# MicroController.net
KiCad netlist of a schematic drawn in Altium Designer
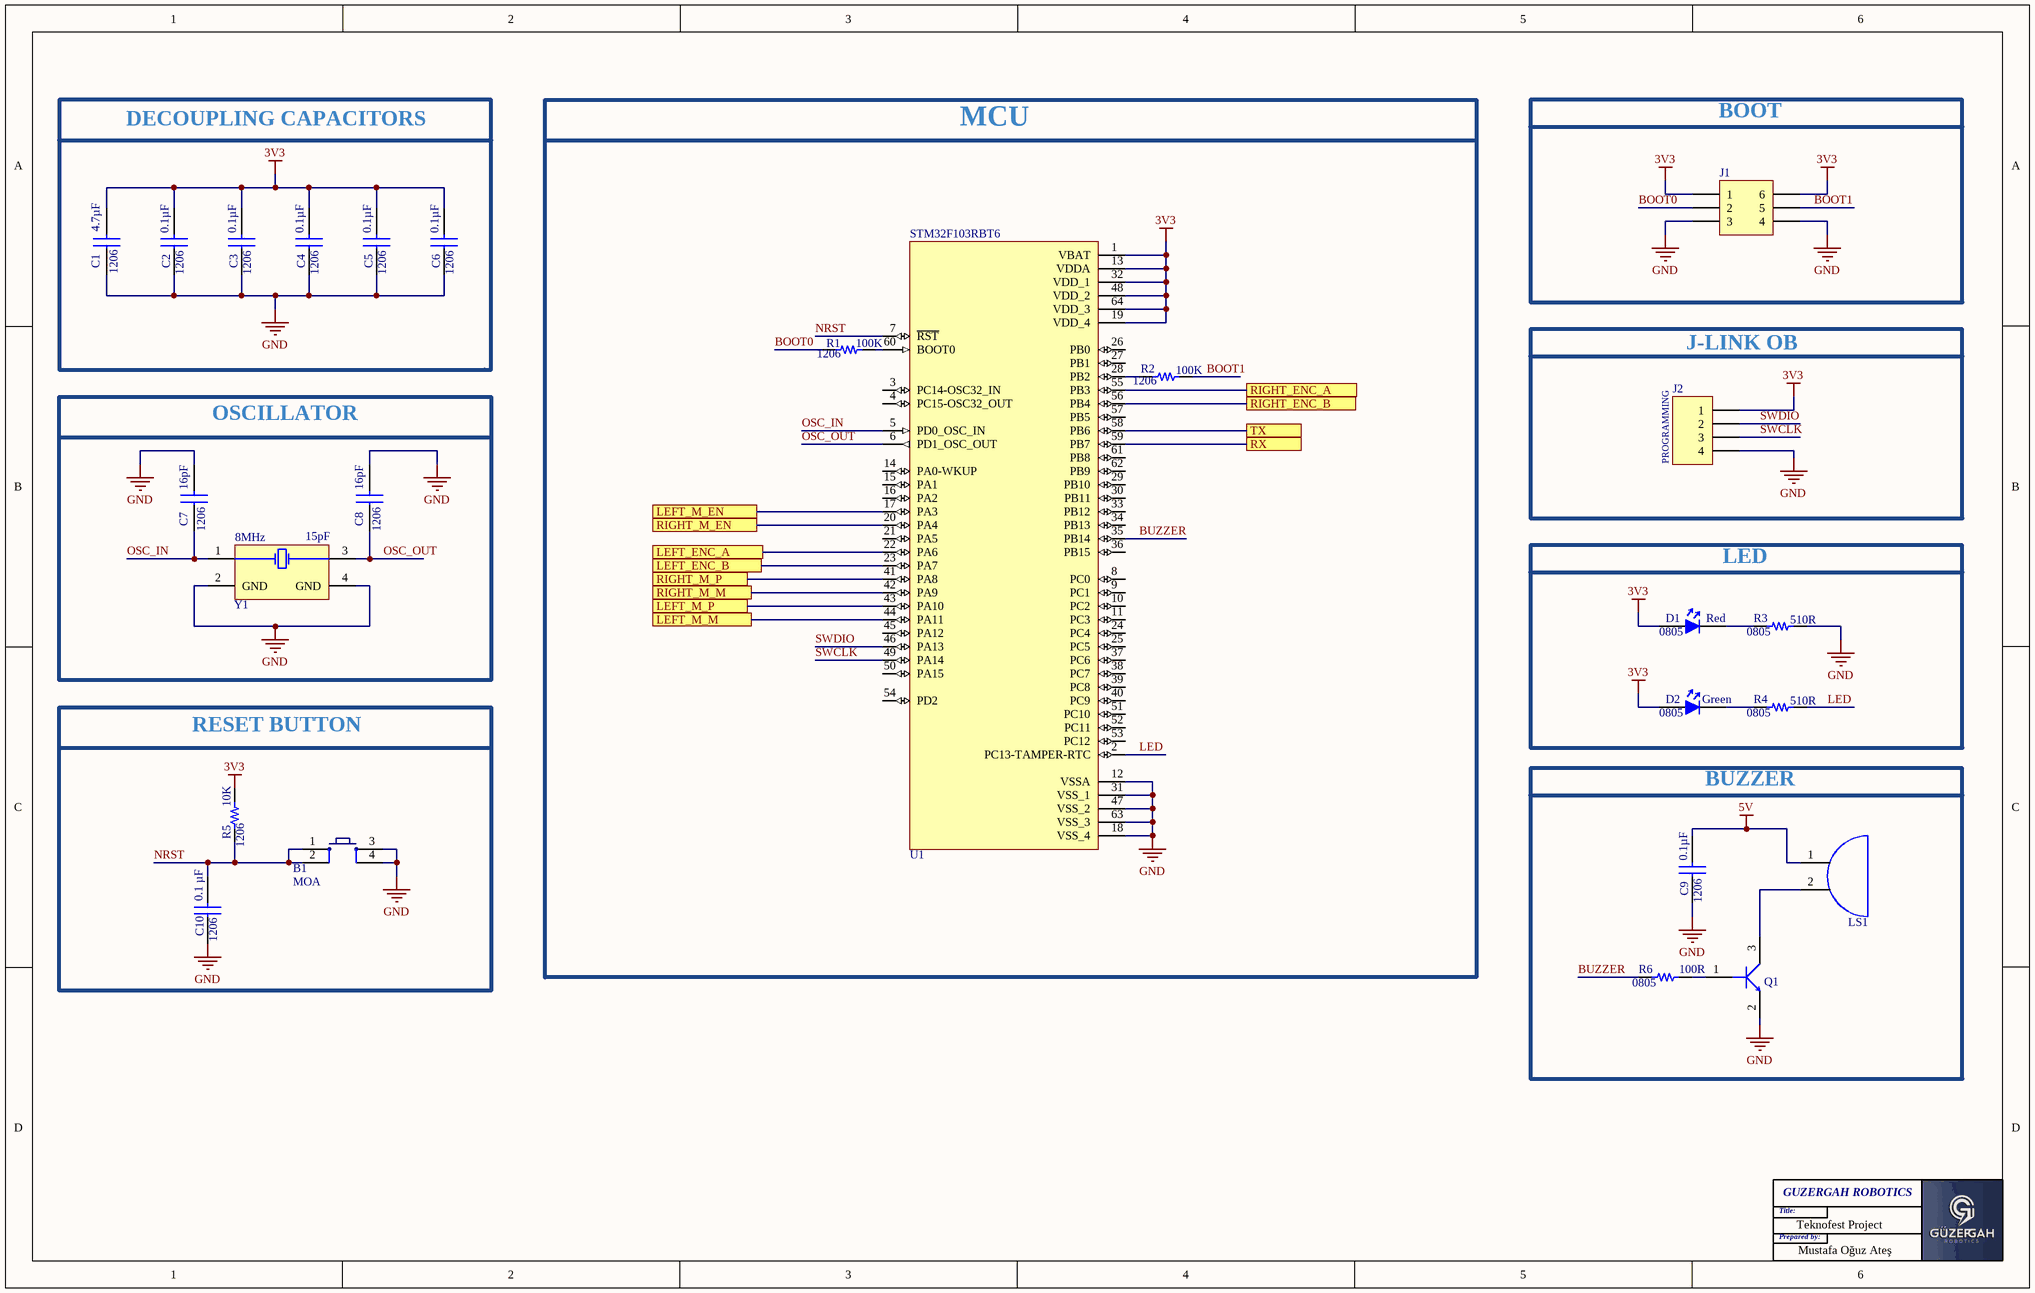
[diagram p0: MicroController.SchDoc]

(export (version "E")
  (design (tool "Eeschema 10.0.6"))
  (components
    (comp (ref "B1")
      (value "Push Button")
      (footprint "PUSH BUTTON-SMD")
      (description "KOMPONENT SEÇİLMEDİ SMD Push Button")
      (fields (field (name "DESIGNED BY") "MOA"))
      (libsource (lib "TeknoFest") (part "Push Button"))
    )
    (comp (ref "C1")
      (value "4.7µF")
      (footprint "CAP_1206_4.7uF")
      (description "CAP CER 4.7 uF 1206")
      (fields (field (name "PACKAGE / CASE") "1206"))
      (libsource (lib "TeknoFest") (part "CAP_1206_4.7uF"))
    )
    (comp (ref "C2")
      (value "0.1µF")
      (footprint "CAP_1206_0.1uF")
      (description "CAP CER 0.1 uF 1206")
      (fields (field (name "PACKAGE / CASE") "1206") (field (name "Comment") "CAP_1206_0.1uF"))
      (libsource (lib "TeknoFest") (part "CAP_1206_0.1uF"))
    )
    (comp (ref "C3")
      (value "0.1µF")
      (footprint "CAP_1206_0.1uF")
      (description "CAP CER 0.1 uF 1206")
      (fields (field (name "PACKAGE / CASE") "1206") (field (name "Comment") "CAP_1206_0.1uF"))
      (libsource (lib "TeknoFest") (part "CAP_1206_0.1uF"))
    )
    (comp (ref "C4")
      (value "0.1µF")
      (footprint "CAP_1206_0.1uF")
      (description "CAP CER 0.1 uF 1206")
      (fields (field (name "PACKAGE / CASE") "1206") (field (name "Comment") "CAP_1206_0.1uF"))
      (libsource (lib "TeknoFest") (part "CAP_1206_0.1uF"))
    )
    (comp (ref "C5")
      (value "0.1µF")
      (footprint "CAP_1206_0.1uF")
      (description "CAP CER 0.1 uF 1206")
      (fields (field (name "PACKAGE / CASE") "1206") (field (name "Comment") "CAP_1206_0.1uF"))
      (libsource (lib "TeknoFest") (part "CAP_1206_0.1uF"))
    )
    (comp (ref "C6")
      (value "0.1µF")
      (footprint "CAP_1206_0.1uF")
      (description "CAP CER 0.1 uF 1206")
      (fields (field (name "PACKAGE / CASE") "1206") (field (name "Comment") "CAP_1206_0.1uF"))
      (libsource (lib "TeknoFest") (part "CAP_1206_0.1uF"))
    )
    (comp (ref "C7")
      (value "16pF")
      (footprint "CAP_1206_16pF")
      (description "CAP CER 16pF 1206")
      (fields (field (name "PACKAGE / CASE") "1206") (field (name "Comment") "CAP_1206_16pF"))
      (libsource (lib "TeknoFest") (part "CAP_1206_16pF"))
    )
    (comp (ref "C8")
      (value "16pF")
      (footprint "CAP_1206_16pF")
      (description "CAP CER 16pF 1206")
      (fields (field (name "PACKAGE / CASE") "1206") (field (name "Comment") "CAP_1206_16pF"))
      (libsource (lib "TeknoFest") (part "CAP_1206_16pF"))
    )
    (comp (ref "C9")
      (value "0.1µF")
      (footprint "CAP_1206_0.1uF")
      (description "CAP CER 0.1 uF 1206")
      (fields (field (name "PACKAGE / CASE") "1206") (field (name "Comment") "CAP_1206_0.1uF"))
      (libsource (lib "TeknoFest") (part "CAP_1206_0.1uF"))
    )
    (comp (ref "C10")
      (value "0.1 µF")
      (footprint "CAP_1206_0.1uF")
      (description "CAP CER 0.1 uF 1206")
      (fields (field (name "PACKAGE / CASE") "1206") (field (name "Comment") "CAP_1206_0.1uF"))
      (libsource (lib "TeknoFest") (part "CAP_1206_0.1uF"))
    )
    (comp (ref "D1")
      (value "LED RED 0805")
      (footprint "LED_RED_0805")
      (description "KOMPONENT SEÇİLMEDİ")
      (fields
        (field (name "MANUFACTURER") "Osram Opto")
        (field (name "MANUFACTURER PART NUMBER") "LH R974-LP-1")
        (field (name "PACKAGE / CASE") "0805")
        (field (name "ILLUMINATION COLOR") "Red")
        (field (name "DESIGNED BY") "Mustafa")
      )
      (libsource (lib "TeknoFest") (part "LED RED 0805"))
    )
    (comp (ref "D2")
      (value "LED GREEN 0805")
      (footprint "LED_GREEN_0805")
      (description "KOMPONENT SEÇİLMEDİ")
      (fields
        (field (name "MANUFACTURER") "Vishay Lite-On")
        (field (name "MANUFACTURER PART NUMBER") "LTST-C171GKT")
        (field (name "PACKAGE / CASE") "0805")
        (field (name "COLOR") "Green")
        (field (name "DESIGNED BY") "Mustafa")
      )
      (libsource (lib "TeknoFest") (part "LED GREEN 0805"))
    )
    (comp (ref "J1")
      (value "L-KLS1-208Y-5.0-2-06-W-8")
      (footprint "BOOT_HEADER_2.54MM_2X3PINS")
      (description "FEMALE HEADER 6PIN(2X3) 2.54MM THT V/T 8x7.62 TUBE")
      (libsource (lib "TeknoFest") (part "BOOT_HEADER"))
    )
    (comp (ref "J2")
      (value "DS1023-1X4S21")
      (footprint "J-LINK OB")
      (description "FEMALE HEADER 4PIN(1x4) 2.54mm THT V/T TRAY")
      (libsource (lib "TeknoFest") (part "J-LINK OB"))
    )
    (comp (ref "LS1")
      (value "CMI-9605IC-0580T")
      (footprint "BUZZER")
      (description "Audio Buzzer Magnetic 3VDC 7VDC 30mA 5VDC 85dB 2600Hz to 2800Hz Through Hole Pin Box")
      (fields (field (name "MANUFACTURER") "CUI Devices") (field (name "DESIGNED BY") "MOA"))
      (libsource (lib "TeknoFest") (part "BUZZER"))
    )
    (comp (ref "Q1")
      (value "MMBT3904-7-F")
      (footprint "SOT-23F")
      (description "MMBT3904-7-F - TRANSISTOR DIS.200mA 40V NPN SOT23 SMT/ ÖZDİSAN")
      (fields (field (name "MANUFACTURER") "Diodes Zetex") (field (name "DESIGNED BY") "MOA"))
      (libsource (lib "TeknoFest") (part "BJT_NPN_TRANSISTOR"))
    )
    (comp (ref "R1")
      (value "100K")
      (footprint "RES_1206_100K")
      (description "RES 1206 100K ohm")
      (fields (field (name "PACKAGE / CASE") "1206") (field (name "Comment") "RES_1206_10K"))
      (libsource (lib "TeknoFest") (part "RES_1206_100K"))
    )
    (comp (ref "R2")
      (value "100K")
      (footprint "RES_1206_100K")
      (description "RES 1206 100K ohm")
      (fields (field (name "PACKAGE / CASE") "1206") (field (name "Comment") "RES_1206_10K"))
      (libsource (lib "TeknoFest") (part "RES_1206_100K"))
    )
    (comp (ref "R3")
      (value "510R")
      (footprint "RES_0805_510R")
      (description "RES 0805 510 ohm")
      (fields (field (name "PACKAGE / CASE") "0805") (field (name "Comment") "RES_0805_510R"))
      (libsource (lib "TeknoFest") (part "RES_0805_510R"))
    )
    (comp (ref "R4")
      (value "510R")
      (footprint "RES_0805_510R")
      (description "RES 0805 510 ohm")
      (fields (field (name "PACKAGE / CASE") "0805") (field (name "Comment") "RES_0805_510R"))
      (libsource (lib "TeknoFest") (part "RES_0805_510R"))
    )
    (comp (ref "R5")
      (value "10K")
      (footprint "RES_1206_10k")
      (description "RES 1206 10K ohm")
      (fields (field (name "PACKAGE / CASE") "1206") (field (name "Comment") "RES_1206_10K"))
      (libsource (lib "TeknoFest") (part "RES_1206_10K"))
    )
    (comp (ref "R6")
      (value "100R")
      (footprint "RES_0805_100R")
      (description "RES 0805 100 ohm")
      (fields (field (name "PACKAGE / CASE") "0805") (field (name "Comment") "RES_0805_100R"))
      (libsource (lib "TeknoFest") (part "RES_0805_100R"))
    )
    (comp (ref "U1")
      (value "STM32F103RBT6")
      (footprint "LQFP-64")
      (description "STM32F103RTB6 LQFP-64")
      (fields (field (name "MF") "STMicroelectronics") (field (name "DESIGNED BY") "MOA"))
      (libsource (lib "TeknoFest") (part "STM32F103RBT6"))
    )
    (comp (ref "Y1")
      (value "ECS-2033-080-AU")
      (footprint "8MHz-OSC")
      (description "CRYSTAL OSCILLATOR XO 8.0000MHZ CMOS SMD")
      (fields
        (field (name "FREQUENCY") "8MHz")
        (field (name "CAPACITANCE") "15pF")
        (field (name "DESIGNED BY") "MOA")
      )
      (libsource (lib "TeknoFest") (part "OSI_8MHz_15pF"))
    )
  )
  (nets
    (net (code "1") (name "/BOOT0") (class "Default")
      (node (ref "J1") (pin "2") (pinfunction "2_2") (pintype "passive"))
      (node (ref "R1") (pin "1") (pinfunction "1_1") (pintype "passive"))
    )
    (net (code "2") (name "/BOOT1") (class "Default")
      (node (ref "J1") (pin "5") (pinfunction "5_5") (pintype "passive"))
      (node (ref "R2") (pin "2") (pinfunction "2_2") (pintype "passive"))
    )
    (net (code "3") (name "/BUZZER") (class "Default")
      (node (ref "R6") (pin "1") (pinfunction "1_1") (pintype "passive"))
      (node (ref "U1") (pin "35") (pinfunction "PB14_35") (pintype "bidirectional"))
    )
    (net (code "4") (name "/LED") (class "Default")
      (node (ref "R4") (pin "2") (pinfunction "2_2") (pintype "passive"))
      (node (ref "U1") (pin "2") (pinfunction "PC13-TAMPER-RTC_2") (pintype "bidirectional"))
    )
    (net (code "5") (name "/LEFT_ENC_A") (class "Default")
      (node (ref "U1") (pin "22") (pinfunction "PA6_22") (pintype "bidirectional"))
    )
    (net (code "6") (name "/LEFT_ENC_B") (class "Default")
      (node (ref "U1") (pin "23") (pinfunction "PA7_23") (pintype "bidirectional"))
    )
    (net (code "7") (name "/LEFT_M_EN") (class "Default")
      (node (ref "U1") (pin "17") (pinfunction "PA3_17") (pintype "bidirectional"))
    )
    (net (code "8") (name "/LEFT_M_M") (class "Default")
      (node (ref "U1") (pin "44") (pinfunction "PA11_44") (pintype "bidirectional"))
    )
    (net (code "9") (name "/LEFT_M_P") (class "Default")
      (node (ref "U1") (pin "43") (pinfunction "PA10_43") (pintype "bidirectional"))
    )
    (net (code "10") (name "/NRST") (class "Default")
      (node (ref "B1") (pin "1") (pinfunction "1_1") (pintype "passive"))
      (node (ref "B1") (pin "2") (pinfunction "2_2") (pintype "passive"))
      (node (ref "C10") (pin "2") (pinfunction "2_2") (pintype "passive"))
      (node (ref "R5") (pin "1") (pinfunction "1_1") (pintype "passive"))
      (node (ref "U1") (pin "7") (pinfunction "~{RST}_7") (pintype "bidirectional"))
    )
    (net (code "11") (name "/OSC_IN") (class "Default")
      (node (ref "C7") (pin "1") (pinfunction "1_1") (pintype "passive"))
      (node (ref "U1") (pin "5") (pinfunction "PD0_OSC_IN_5") (pintype "input"))
      (node (ref "Y1") (pin "1") (pinfunction "Tristate_1") (pintype "passive"))
    )
    (net (code "12") (name "/OSC_OUT") (class "Default")
      (node (ref "C8") (pin "1") (pinfunction "1_1") (pintype "passive"))
      (node (ref "U1") (pin "6") (pinfunction "PD1_OSC_OUT_6") (pintype "output"))
      (node (ref "Y1") (pin "3") (pinfunction "OUT_3") (pintype "passive"))
    )
    (net (code "13") (name "/RIGHT_ENC_A") (class "Default")
      (node (ref "U1") (pin "55") (pinfunction "PB3_55") (pintype "bidirectional"))
    )
    (net (code "14") (name "/RIGHT_ENC_B") (class "Default")
      (node (ref "U1") (pin "56") (pinfunction "PB4_56") (pintype "bidirectional"))
    )
    (net (code "15") (name "/RIGHT_M_EN") (class "Default")
      (node (ref "U1") (pin "20") (pinfunction "PA4_20") (pintype "bidirectional"))
    )
    (net (code "16") (name "/RIGHT_M_M") (class "Default")
      (node (ref "U1") (pin "42") (pinfunction "PA9_42") (pintype "bidirectional"))
    )
    (net (code "17") (name "/RIGHT_M_P") (class "Default")
      (node (ref "U1") (pin "41") (pinfunction "PA8_41") (pintype "bidirectional"))
    )
    (net (code "18") (name "/RX") (class "Default")
      (node (ref "U1") (pin "59") (pinfunction "PB7_59") (pintype "bidirectional"))
    )
    (net (code "19") (name "/SWCLK") (class "Default")
      (node (ref "J2") (pin "3") (pinfunction "3_3") (pintype "passive"))
      (node (ref "U1") (pin "49") (pinfunction "PA14_49") (pintype "bidirectional"))
    )
    (net (code "20") (name "/SWDIO") (class "Default")
      (node (ref "J2") (pin "2") (pinfunction "2_2") (pintype "passive"))
      (node (ref "U1") (pin "46") (pinfunction "PA13_46") (pintype "bidirectional"))
    )
    (net (code "21") (name "/TX") (class "Default")
      (node (ref "U1") (pin "58") (pinfunction "PB6_58") (pintype "bidirectional"))
    )
    (net (code "22") (name "3V3") (class "Default")
      (node (ref "C1") (pin "2") (pinfunction "2_2") (pintype "passive"))
      (node (ref "C2") (pin "2") (pinfunction "2_2") (pintype "passive"))
      (node (ref "C3") (pin "2") (pinfunction "2_2") (pintype "passive"))
      (node (ref "C4") (pin "2") (pinfunction "2_2") (pintype "passive"))
      (node (ref "C5") (pin "2") (pinfunction "2_2") (pintype "passive"))
      (node (ref "C6") (pin "2") (pinfunction "2_2") (pintype "passive"))
      (node (ref "D1") (pin "2") (pinfunction "2_2") (pintype "power_in"))
      (node (ref "D2") (pin "2") (pinfunction "2_2") (pintype "power_in"))
      (node (ref "J1") (pin "1") (pinfunction "1_1") (pintype "passive"))
      (node (ref "J1") (pin "6") (pinfunction "6_6") (pintype "passive"))
      (node (ref "J2") (pin "1") (pinfunction "1_1") (pintype "passive"))
      (node (ref "R5") (pin "2") (pinfunction "2_2") (pintype "passive"))
      (node (ref "U1") (pin "1") (pinfunction "VBAT_1") (pintype "power_in"))
      (node (ref "U1") (pin "13") (pinfunction "VDDA_13") (pintype "power_in"))
      (node (ref "U1") (pin "19") (pinfunction "VDD_4_19") (pintype "power_in"))
      (node (ref "U1") (pin "32") (pinfunction "VDD_1_32") (pintype "power_in"))
      (node (ref "U1") (pin "48") (pinfunction "VDD_2_48") (pintype "power_in"))
      (node (ref "U1") (pin "64") (pinfunction "VDD_3_64") (pintype "power_in"))
    )
    (net (code "23") (name "5V") (class "Default")
      (node (ref "C9") (pin "2") (pinfunction "2_2") (pintype "passive"))
      (node (ref "LS1") (pin "1") (pinfunction "1_1") (pintype "passive"))
    )
    (net (code "24") (name "GND") (class "Default")
      (node (ref "B1") (pin "3") (pinfunction "3_3") (pintype "passive"))
      (node (ref "B1") (pin "4") (pinfunction "4_4") (pintype "passive"))
      (node (ref "C1") (pin "1") (pinfunction "1_1") (pintype "passive"))
      (node (ref "C10") (pin "1") (pinfunction "1_1") (pintype "passive"))
      (node (ref "C2") (pin "1") (pinfunction "1_1") (pintype "passive"))
      (node (ref "C3") (pin "1") (pinfunction "1_1") (pintype "passive"))
      (node (ref "C4") (pin "1") (pinfunction "1_1") (pintype "passive"))
      (node (ref "C5") (pin "1") (pinfunction "1_1") (pintype "passive"))
      (node (ref "C6") (pin "1") (pinfunction "1_1") (pintype "passive"))
      (node (ref "C7") (pin "2") (pinfunction "2_2") (pintype "passive"))
      (node (ref "C8") (pin "2") (pinfunction "2_2") (pintype "passive"))
      (node (ref "C9") (pin "1") (pinfunction "1_1") (pintype "passive"))
      (node (ref "J1") (pin "3") (pinfunction "3_3") (pintype "passive"))
      (node (ref "J1") (pin "4") (pinfunction "4_4") (pintype "passive"))
      (node (ref "J2") (pin "4") (pinfunction "4_4") (pintype "passive"))
      (node (ref "Q1") (pin "2") (pinfunction "E_2") (pintype "power_in"))
      (node (ref "R3") (pin "2") (pinfunction "2_2") (pintype "passive"))
      (node (ref "U1") (pin "12") (pinfunction "VSSA_12") (pintype "power_in"))
      (node (ref "U1") (pin "18") (pinfunction "VSS_4_18") (pintype "power_in"))
      (node (ref "U1") (pin "31") (pinfunction "VSS_1_31") (pintype "power_in"))
      (node (ref "U1") (pin "47") (pinfunction "VSS_2_47") (pintype "power_in"))
      (node (ref "U1") (pin "63") (pinfunction "VSS_3_63") (pintype "power_in"))
      (node (ref "Y1") (pin "2") (pinfunction "GND_2") (pintype "passive"))
      (node (ref "Y1") (pin "4") (pinfunction "GND_4") (pintype "passive"))
    )
    (net (code "25") (name "Net-(D1-Pad1)") (class "Default")
      (node (ref "D1") (pin "1") (pinfunction "1_1") (pintype "power_in"))
      (node (ref "R3") (pin "1") (pinfunction "1_1") (pintype "passive"))
    )
    (net (code "26") (name "Net-(D2-Pad1)") (class "Default")
      (node (ref "D2") (pin "1") (pinfunction "1_1") (pintype "power_in"))
      (node (ref "R4") (pin "1") (pinfunction "1_1") (pintype "passive"))
    )
    (net (code "27") (name "Net-(Q1-B)") (class "Default")
      (node (ref "Q1") (pin "1") (pinfunction "B_1") (pintype "power_in"))
      (node (ref "R6") (pin "2") (pinfunction "2_2") (pintype "passive"))
    )
    (net (code "28") (name "Net-(Q1-C)") (class "Default")
      (node (ref "LS1") (pin "2") (pinfunction "2_2") (pintype "passive"))
      (node (ref "Q1") (pin "3") (pinfunction "C_3") (pintype "power_in"))
    )
    (net (code "29") (name "Net-(U1-BOOT0)") (class "Default")
      (node (ref "R1") (pin "2") (pinfunction "2_2") (pintype "passive"))
      (node (ref "U1") (pin "60") (pinfunction "BOOT0_60") (pintype "input"))
    )
    (net (code "30") (name "Net-(U1-PB2)") (class "Default")
      (node (ref "R2") (pin "1") (pinfunction "1_1") (pintype "passive"))
      (node (ref "U1") (pin "28") (pinfunction "PB2_28") (pintype "bidirectional"))
    )
    (net (code "31") (name "unconnected-(U1-PA0-WKUP-Pad14)") (class "Default")
      (node (ref "U1") (pin "14") (pinfunction "PA0-WKUP_14") (pintype "bidirectional"))
    )
    (net (code "32") (name "unconnected-(U1-PA1-Pad15)") (class "Default")
      (node (ref "U1") (pin "15") (pinfunction "PA1_15") (pintype "bidirectional"))
    )
    (net (code "33") (name "unconnected-(U1-PA2-Pad16)") (class "Default")
      (node (ref "U1") (pin "16") (pinfunction "PA2_16") (pintype "bidirectional"))
    )
    (net (code "34") (name "unconnected-(U1-PA5-Pad21)") (class "Default")
      (node (ref "U1") (pin "21") (pinfunction "PA5_21") (pintype "bidirectional"))
    )
    (net (code "35") (name "unconnected-(U1-PA12-Pad45)") (class "Default")
      (node (ref "U1") (pin "45") (pinfunction "PA12_45") (pintype "bidirectional"))
    )
    (net (code "36") (name "unconnected-(U1-PA15-Pad50)") (class "Default")
      (node (ref "U1") (pin "50") (pinfunction "PA15_50") (pintype "bidirectional"))
    )
    (net (code "37") (name "unconnected-(U1-PB0-Pad26)") (class "Default")
      (node (ref "U1") (pin "26") (pinfunction "PB0_26") (pintype "bidirectional"))
    )
    (net (code "38") (name "unconnected-(U1-PB1-Pad27)") (class "Default")
      (node (ref "U1") (pin "27") (pinfunction "PB1_27") (pintype "bidirectional"))
    )
    (net (code "39") (name "unconnected-(U1-PB5-Pad57)") (class "Default")
      (node (ref "U1") (pin "57") (pinfunction "PB5_57") (pintype "bidirectional"))
    )
    (net (code "40") (name "unconnected-(U1-PB8-Pad61)") (class "Default")
      (node (ref "U1") (pin "61") (pinfunction "PB8_61") (pintype "bidirectional"))
    )
    (net (code "41") (name "unconnected-(U1-PB9-Pad62)") (class "Default")
      (node (ref "U1") (pin "62") (pinfunction "PB9_62") (pintype "bidirectional"))
    )
    (net (code "42") (name "unconnected-(U1-PB10-Pad29)") (class "Default")
      (node (ref "U1") (pin "29") (pinfunction "PB10_29") (pintype "bidirectional"))
    )
    (net (code "43") (name "unconnected-(U1-PB11-Pad30)") (class "Default")
      (node (ref "U1") (pin "30") (pinfunction "PB11_30") (pintype "bidirectional"))
    )
    (net (code "44") (name "unconnected-(U1-PB12-Pad33)") (class "Default")
      (node (ref "U1") (pin "33") (pinfunction "PB12_33") (pintype "bidirectional"))
    )
    (net (code "45") (name "unconnected-(U1-PB13-Pad34)") (class "Default")
      (node (ref "U1") (pin "34") (pinfunction "PB13_34") (pintype "bidirectional"))
    )
    (net (code "46") (name "unconnected-(U1-PB15-Pad36)") (class "Default")
      (node (ref "U1") (pin "36") (pinfunction "PB15_36") (pintype "bidirectional"))
    )
    (net (code "47") (name "unconnected-(U1-PC0-Pad8)") (class "Default")
      (node (ref "U1") (pin "8") (pinfunction "PC0_8") (pintype "bidirectional"))
    )
    (net (code "48") (name "unconnected-(U1-PC1-Pad9)") (class "Default")
      (node (ref "U1") (pin "9") (pinfunction "PC1_9") (pintype "bidirectional"))
    )
    (net (code "49") (name "unconnected-(U1-PC2-Pad10)") (class "Default")
      (node (ref "U1") (pin "10") (pinfunction "PC2_10") (pintype "bidirectional"))
    )
    (net (code "50") (name "unconnected-(U1-PC3-Pad11)") (class "Default")
      (node (ref "U1") (pin "11") (pinfunction "PC3_11") (pintype "bidirectional"))
    )
    (net (code "51") (name "unconnected-(U1-PC4-Pad24)") (class "Default")
      (node (ref "U1") (pin "24") (pinfunction "PC4_24") (pintype "bidirectional"))
    )
    (net (code "52") (name "unconnected-(U1-PC5-Pad25)") (class "Default")
      (node (ref "U1") (pin "25") (pinfunction "PC5_25") (pintype "bidirectional"))
    )
    (net (code "53") (name "unconnected-(U1-PC6-Pad37)") (class "Default")
      (node (ref "U1") (pin "37") (pinfunction "PC6_37") (pintype "bidirectional"))
    )
    (net (code "54") (name "unconnected-(U1-PC7-Pad38)") (class "Default")
      (node (ref "U1") (pin "38") (pinfunction "PC7_38") (pintype "bidirectional"))
    )
    (net (code "55") (name "unconnected-(U1-PC8-Pad39)") (class "Default")
      (node (ref "U1") (pin "39") (pinfunction "PC8_39") (pintype "bidirectional"))
    )
    (net (code "56") (name "unconnected-(U1-PC9-Pad40)") (class "Default")
      (node (ref "U1") (pin "40") (pinfunction "PC9_40") (pintype "bidirectional"))
    )
    (net (code "57") (name "unconnected-(U1-PC10-Pad51)") (class "Default")
      (node (ref "U1") (pin "51") (pinfunction "PC10_51") (pintype "bidirectional"))
    )
    (net (code "58") (name "unconnected-(U1-PC11-Pad52)") (class "Default")
      (node (ref "U1") (pin "52") (pinfunction "PC11_52") (pintype "bidirectional"))
    )
    (net (code "59") (name "unconnected-(U1-PC12-Pad53)") (class "Default")
      (node (ref "U1") (pin "53") (pinfunction "PC12_53") (pintype "bidirectional"))
    )
    (net (code "60") (name "unconnected-(U1-PC14-OSC32_IN-Pad3)") (class "Default")
      (node (ref "U1") (pin "3") (pinfunction "PC14-OSC32_IN_3") (pintype "bidirectional"))
    )
    (net (code "61") (name "unconnected-(U1-PC15-OSC32_OUT-Pad4)") (class "Default")
      (node (ref "U1") (pin "4") (pinfunction "PC15-OSC32_OUT_4") (pintype "bidirectional"))
    )
    (net (code "62") (name "unconnected-(U1-PD2-Pad54)") (class "Default")
      (node (ref "U1") (pin "54") (pinfunction "PD2_54") (pintype "bidirectional"))
    )
  )
)
